# Irrigate4.net
KiCad netlist of a schematic drawn in EAGLE
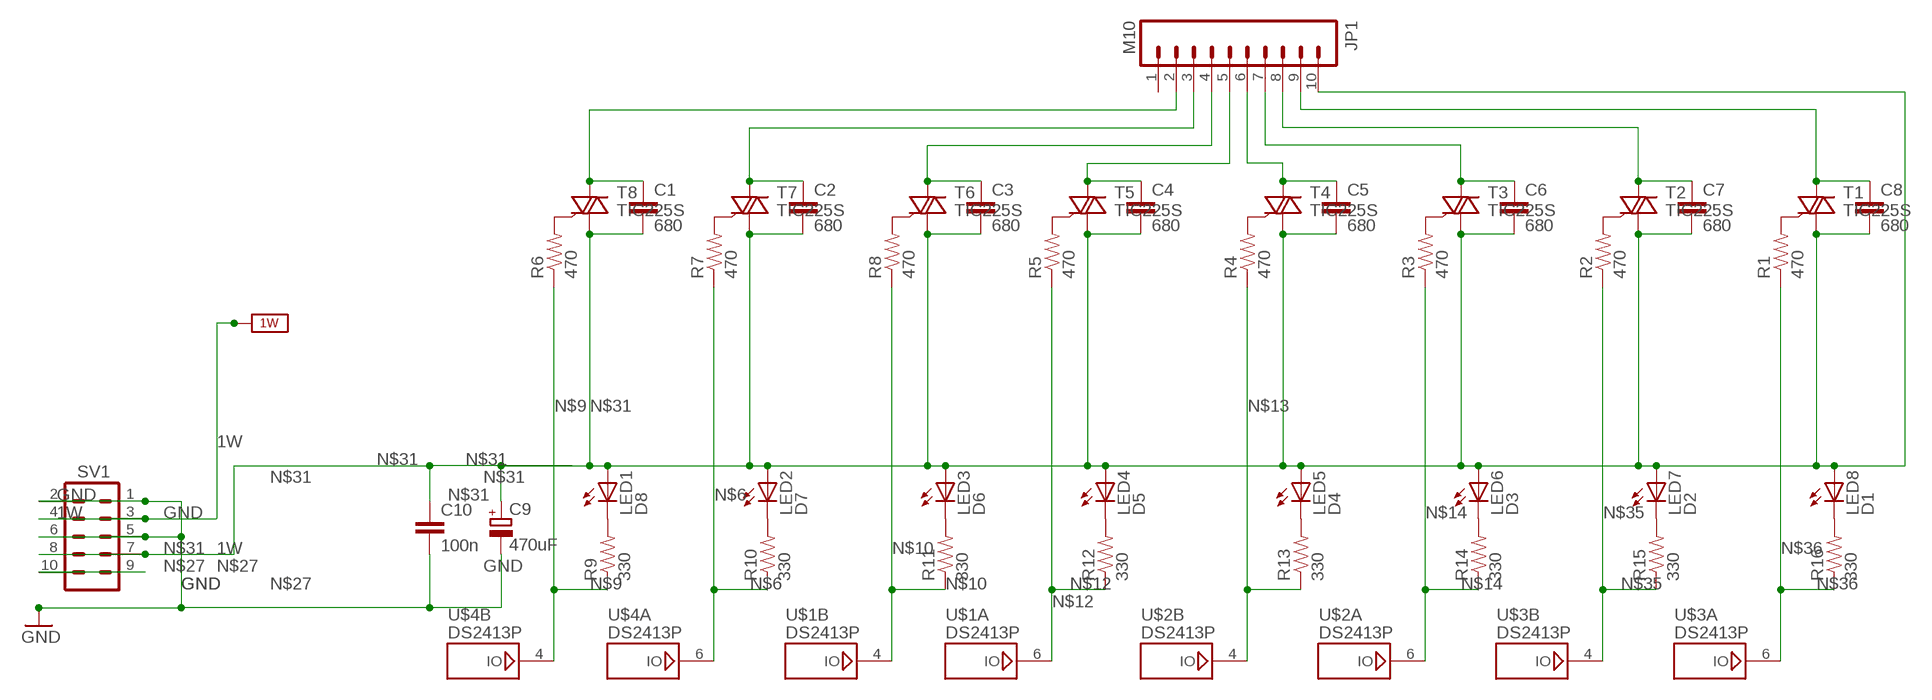
[diagram p0: schematic, sheet 1]

(export (version "E")
  (design (tool "Eeschema 10.0.6"))
  (components
    (comp (ref "C1")
      (value "680")
      (footprint "eagle-import:C050-045X075")
      (libsource (lib "eagle-import") (part "C-EU050-045X075"))
    )
    (comp (ref "C2")
      (value "680")
      (footprint "eagle-import:C050-045X075")
      (libsource (lib "eagle-import") (part "C-EU050-045X075"))
    )
    (comp (ref "C3")
      (value "680")
      (footprint "eagle-import:C050-045X075")
      (libsource (lib "eagle-import") (part "C-EU050-045X075"))
    )
    (comp (ref "C4")
      (value "680")
      (footprint "eagle-import:C050-045X075")
      (libsource (lib "eagle-import") (part "C-EU050-045X075"))
    )
    (comp (ref "C5")
      (value "680")
      (footprint "eagle-import:C050-045X075")
      (libsource (lib "eagle-import") (part "C-EU050-045X075"))
    )
    (comp (ref "C6")
      (value "680")
      (footprint "eagle-import:C050-045X075")
      (libsource (lib "eagle-import") (part "C-EU050-045X075"))
    )
    (comp (ref "C7")
      (value "680")
      (footprint "eagle-import:C050-045X075")
      (libsource (lib "eagle-import") (part "C-EU050-045X075"))
    )
    (comp (ref "C8")
      (value "680")
      (footprint "eagle-import:C050-045X075")
      (libsource (lib "eagle-import") (part "C-EU050-045X075"))
    )
    (comp (ref "C9")
      (value "470uF")
      (footprint "eagle-import:E5-8,5")
      (libsource (lib "eagle-import") (part "CPOL-EUE5-8.5"))
    )
    (comp (ref "C10")
      (value "100n")
      (footprint "eagle-import:C050-024X044")
      (libsource (lib "eagle-import") (part "C-EU050-024X044"))
    )
    (comp (ref "JP1")
      (value "M10")
      (footprint "eagle-import:10X10MM")
      (libsource (lib "eagle-import") (part "M10"))
    )
    (comp (ref "LED1")
      (value "D8")
      (footprint "eagle-import:LED3MM")
      (libsource (lib "eagle-import") (part "LED3MM"))
    )
    (comp (ref "LED2")
      (value "D7")
      (footprint "eagle-import:LED3MM")
      (libsource (lib "eagle-import") (part "LED3MM"))
    )
    (comp (ref "LED3")
      (value "D6")
      (footprint "eagle-import:LED3MM")
      (libsource (lib "eagle-import") (part "LED3MM"))
    )
    (comp (ref "LED4")
      (value "D5")
      (footprint "eagle-import:LED3MM")
      (libsource (lib "eagle-import") (part "LED3MM"))
    )
    (comp (ref "LED5")
      (value "D4")
      (footprint "eagle-import:LED3MM")
      (libsource (lib "eagle-import") (part "LED3MM"))
    )
    (comp (ref "LED6")
      (value "D3")
      (footprint "eagle-import:LED3MM")
      (libsource (lib "eagle-import") (part "LED3MM"))
    )
    (comp (ref "LED7")
      (value "D2")
      (footprint "eagle-import:LED3MM")
      (libsource (lib "eagle-import") (part "LED3MM"))
    )
    (comp (ref "LED8")
      (value "D1")
      (footprint "eagle-import:LED3MM")
      (libsource (lib "eagle-import") (part "LED3MM"))
    )
    (comp (ref "R1")
      (value "470")
      (footprint "eagle-import:AXIAL-0.3")
      (libsource (lib "eagle-import") (part "RESISTORPTH1"))
    )
    (comp (ref "R2")
      (value "470")
      (footprint "eagle-import:AXIAL-0.3")
      (libsource (lib "eagle-import") (part "RESISTORPTH1"))
    )
    (comp (ref "R3")
      (value "470")
      (footprint "eagle-import:AXIAL-0.3")
      (libsource (lib "eagle-import") (part "RESISTORPTH1"))
    )
    (comp (ref "R4")
      (value "470")
      (footprint "eagle-import:AXIAL-0.3")
      (libsource (lib "eagle-import") (part "RESISTORPTH1"))
    )
    (comp (ref "R5")
      (value "470")
      (footprint "eagle-import:AXIAL-0.3")
      (libsource (lib "eagle-import") (part "RESISTORPTH1"))
    )
    (comp (ref "R6")
      (value "470")
      (footprint "eagle-import:AXIAL-0.3")
      (libsource (lib "eagle-import") (part "RESISTORPTH1"))
    )
    (comp (ref "R7")
      (value "470")
      (footprint "eagle-import:AXIAL-0.3")
      (libsource (lib "eagle-import") (part "RESISTORPTH1"))
    )
    (comp (ref "R8")
      (value "470")
      (footprint "eagle-import:AXIAL-0.3")
      (libsource (lib "eagle-import") (part "RESISTORPTH1"))
    )
    (comp (ref "R9")
      (value "330")
      (footprint "eagle-import:AXIAL-0.3")
      (libsource (lib "eagle-import") (part "RESISTORPTH1"))
    )
    (comp (ref "R10")
      (value "330")
      (footprint "eagle-import:AXIAL-0.3")
      (libsource (lib "eagle-import") (part "RESISTORPTH1"))
    )
    (comp (ref "R11")
      (value "330")
      (footprint "eagle-import:AXIAL-0.3")
      (libsource (lib "eagle-import") (part "RESISTORPTH1"))
    )
    (comp (ref "R12")
      (value "330")
      (footprint "eagle-import:AXIAL-0.3")
      (libsource (lib "eagle-import") (part "RESISTORPTH1"))
    )
    (comp (ref "R13")
      (value "330")
      (footprint "eagle-import:AXIAL-0.3")
      (libsource (lib "eagle-import") (part "RESISTORPTH1"))
    )
    (comp (ref "R14")
      (value "330")
      (footprint "eagle-import:AXIAL-0.3")
      (libsource (lib "eagle-import") (part "RESISTORPTH1"))
    )
    (comp (ref "R15")
      (value "330")
      (footprint "eagle-import:AXIAL-0.3")
      (libsource (lib "eagle-import") (part "RESISTORPTH1"))
    )
    (comp (ref "R16")
      (value "330")
      (footprint "eagle-import:AXIAL-0.3")
      (libsource (lib "eagle-import") (part "RESISTORPTH1"))
    )
    (comp (ref "SV1")
      (value "M05X2PTH")
      (footprint "eagle-import:AVR_ICSP")
      (libsource (lib "eagle-import") (part "M05X2PTH"))
    )
    (comp (ref "T1")
      (value "TIC225S")
      (footprint "eagle-import:TO220DS")
      (libsource (lib "eagle-import") (part "TIC225S"))
    )
    (comp (ref "T2")
      (value "TIC225S")
      (footprint "eagle-import:TO220DS")
      (libsource (lib "eagle-import") (part "TIC225S"))
    )
    (comp (ref "T3")
      (value "TIC225S")
      (footprint "eagle-import:TO220DS")
      (libsource (lib "eagle-import") (part "TIC225S"))
    )
    (comp (ref "T4")
      (value "TIC225S")
      (footprint "eagle-import:TO220DS")
      (libsource (lib "eagle-import") (part "TIC225S"))
    )
    (comp (ref "T5")
      (value "TIC225S")
      (footprint "eagle-import:TO220DS")
      (libsource (lib "eagle-import") (part "TIC225S"))
    )
    (comp (ref "T6")
      (value "TIC225S")
      (footprint "eagle-import:TO220DS")
      (libsource (lib "eagle-import") (part "TIC225S"))
    )
    (comp (ref "T7")
      (value "TIC225S")
      (footprint "eagle-import:TO220DS")
      (libsource (lib "eagle-import") (part "TIC225S"))
    )
    (comp (ref "T8")
      (value "TIC225S")
      (footprint "eagle-import:TO220DS")
      (libsource (lib "eagle-import") (part "TIC225S"))
    )
    (comp (ref "U$1")
      (value "DS2413P")
      (footprint "eagle-import:TSOC6")
      (libsource (lib "eagle-import") (part "DS2413P"))
    )
    (comp (ref "U$2")
      (value "DS2413P")
      (footprint "eagle-import:TSOC6")
      (libsource (lib "eagle-import") (part "DS2413P"))
    )
    (comp (ref "U$3")
      (value "DS2413P")
      (footprint "eagle-import:TSOC6")
      (libsource (lib "eagle-import") (part "DS2413P"))
    )
    (comp (ref "U$4")
      (value "DS2413P")
      (footprint "eagle-import:TSOC6")
      (libsource (lib "eagle-import") (part "DS2413P"))
    )
  )
  (nets
    (net (code "1") (name "/N$6") (class "Default")
      (node (ref "R10") (pin "P$1") (pinfunction "1_P$1") (pintype "passive"))
      (node (ref "R7") (pin "P$1") (pinfunction "1_P$1") (pintype "passive"))
      (node (ref "U$4") (pin "6") (pinfunction "IO_6") (pintype "open_collector"))
    )
    (net (code "2") (name "/N$9") (class "Default")
      (node (ref "R6") (pin "P$1") (pinfunction "1_P$1") (pintype "passive"))
      (node (ref "R9") (pin "P$1") (pinfunction "1_P$1") (pintype "passive"))
      (node (ref "U$4") (pin "4") (pinfunction "IO_4") (pintype "open_collector"))
    )
    (net (code "3") (name "/N$10") (class "Default")
      (node (ref "R11") (pin "P$1") (pinfunction "1_P$1") (pintype "passive"))
      (node (ref "R8") (pin "P$1") (pinfunction "1_P$1") (pintype "passive"))
      (node (ref "U$1") (pin "4") (pinfunction "IO_4") (pintype "open_collector"))
    )
    (net (code "4") (name "/N$12") (class "Default")
      (node (ref "R12") (pin "P$1") (pinfunction "1_P$1") (pintype "passive"))
      (node (ref "R5") (pin "P$1") (pinfunction "1_P$1") (pintype "passive"))
      (node (ref "U$1") (pin "6") (pinfunction "IO_6") (pintype "open_collector"))
    )
    (net (code "5") (name "/N$13") (class "Default")
      (node (ref "R13") (pin "P$1") (pinfunction "1_P$1") (pintype "passive"))
      (node (ref "R4") (pin "P$1") (pinfunction "1_P$1") (pintype "passive"))
      (node (ref "U$2") (pin "4") (pinfunction "IO_4") (pintype "open_collector"))
    )
    (net (code "6") (name "/N$14") (class "Default")
      (node (ref "R14") (pin "P$1") (pinfunction "1_P$1") (pintype "passive"))
      (node (ref "R3") (pin "P$1") (pinfunction "1_P$1") (pintype "passive"))
      (node (ref "U$2") (pin "6") (pinfunction "IO_6") (pintype "open_collector"))
    )
    (net (code "7") (name "/N$27") (class "Default")
      (node (ref "SV1") (pin "10") (pinfunction "10_10") (pintype "passive"))
      (node (ref "SV1") (pin "9") (pinfunction "9_9") (pintype "passive"))
    )
    (net (code "8") (name "/N$31") (class "Default")
      (node (ref "C1") (pin "2") (pinfunction "2_2") (pintype "passive"))
      (node (ref "C10") (pin "1") (pinfunction "1_1") (pintype "passive"))
      (node (ref "C2") (pin "2") (pinfunction "2_2") (pintype "passive"))
      (node (ref "C3") (pin "2") (pinfunction "2_2") (pintype "passive"))
      (node (ref "C4") (pin "2") (pinfunction "2_2") (pintype "passive"))
      (node (ref "C5") (pin "2") (pinfunction "2_2") (pintype "passive"))
      (node (ref "C6") (pin "2") (pinfunction "2_2") (pintype "passive"))
      (node (ref "C7") (pin "2") (pinfunction "2_2") (pintype "passive"))
      (node (ref "C8") (pin "2") (pinfunction "2_2") (pintype "passive"))
      (node (ref "C9") (pin "+") (pinfunction "+_+") (pintype "passive"))
      (node (ref "JP1") (pin "10") (pinfunction "10_10") (pintype "passive"))
      (node (ref "LED1") (pin "A") (pinfunction "A_A") (pintype "passive"))
      (node (ref "LED2") (pin "A") (pinfunction "A_A") (pintype "passive"))
      (node (ref "LED3") (pin "A") (pinfunction "A_A") (pintype "passive"))
      (node (ref "LED4") (pin "A") (pinfunction "A_A") (pintype "passive"))
      (node (ref "LED5") (pin "A") (pinfunction "A_A") (pintype "passive"))
      (node (ref "LED6") (pin "A") (pinfunction "A_A") (pintype "passive"))
      (node (ref "LED7") (pin "A") (pinfunction "A_A") (pintype "passive"))
      (node (ref "LED8") (pin "A") (pinfunction "A_A") (pintype "passive"))
      (node (ref "SV1") (pin "7") (pinfunction "7_7") (pintype "passive"))
      (node (ref "SV1") (pin "8") (pinfunction "8_8") (pintype "passive"))
      (node (ref "T1") (pin "A1") (pinfunction "A1_A1") (pintype "passive"))
      (node (ref "T2") (pin "A1") (pinfunction "A1_A1") (pintype "passive"))
      (node (ref "T3") (pin "A1") (pinfunction "A1_A1") (pintype "passive"))
      (node (ref "T4") (pin "A1") (pinfunction "A1_A1") (pintype "passive"))
      (node (ref "T5") (pin "A1") (pinfunction "A1_A1") (pintype "passive"))
      (node (ref "T6") (pin "A1") (pinfunction "A1_A1") (pintype "passive"))
      (node (ref "T7") (pin "A1") (pinfunction "A1_A1") (pintype "passive"))
      (node (ref "T8") (pin "A1") (pinfunction "A1_A1") (pintype "passive"))
    )
    (net (code "9") (name "/N$35") (class "Default")
      (node (ref "R15") (pin "P$1") (pinfunction "1_P$1") (pintype "passive"))
      (node (ref "R2") (pin "P$1") (pinfunction "1_P$1") (pintype "passive"))
      (node (ref "U$3") (pin "4") (pinfunction "IO_4") (pintype "open_collector"))
    )
    (net (code "10") (name "/N$36") (class "Default")
      (node (ref "R1") (pin "P$1") (pinfunction "1_P$1") (pintype "passive"))
      (node (ref "R16") (pin "P$1") (pinfunction "1_P$1") (pintype "passive"))
      (node (ref "U$3") (pin "6") (pinfunction "IO_6") (pintype "open_collector"))
    )
    (net (code "11") (name "1W_SUP") (class "Default")
      (node (ref "SV1") (pin "3") (pinfunction "3_3") (pintype "passive"))
      (node (ref "SV1") (pin "4") (pinfunction "4_4") (pintype "passive"))
    )
    (net (code "12") (name "GND") (class "Default")
      (node (ref "C10") (pin "2") (pinfunction "2_2") (pintype "passive"))
      (node (ref "C9") (pin "-") (pinfunction "-_-") (pintype "passive"))
      (node (ref "SV1") (pin "1") (pinfunction "1_1") (pintype "passive"))
      (node (ref "SV1") (pin "2") (pinfunction "2_2") (pintype "passive"))
      (node (ref "SV1") (pin "5") (pinfunction "5_5") (pintype "passive"))
      (node (ref "SV1") (pin "6") (pinfunction "6_6") (pintype "passive"))
    )
    (net (code "13") (name "Net-(C1-Pad1)") (class "Default")
      (node (ref "C1") (pin "1") (pinfunction "1_1") (pintype "passive"))
      (node (ref "JP1") (pin "2") (pinfunction "2_2") (pintype "passive"))
      (node (ref "T8") (pin "A2") (pinfunction "A2_A2") (pintype "passive"))
    )
    (net (code "14") (name "Net-(C2-Pad1)") (class "Default")
      (node (ref "C2") (pin "1") (pinfunction "1_1") (pintype "passive"))
      (node (ref "JP1") (pin "3") (pinfunction "3_3") (pintype "passive"))
      (node (ref "T7") (pin "A2") (pinfunction "A2_A2") (pintype "passive"))
    )
    (net (code "15") (name "Net-(C3-Pad1)") (class "Default")
      (node (ref "C3") (pin "1") (pinfunction "1_1") (pintype "passive"))
      (node (ref "JP1") (pin "4") (pinfunction "4_4") (pintype "passive"))
      (node (ref "T6") (pin "A2") (pinfunction "A2_A2") (pintype "passive"))
    )
    (net (code "16") (name "Net-(C4-Pad1)") (class "Default")
      (node (ref "C4") (pin "1") (pinfunction "1_1") (pintype "passive"))
      (node (ref "JP1") (pin "5") (pinfunction "5_5") (pintype "passive"))
      (node (ref "T5") (pin "A2") (pinfunction "A2_A2") (pintype "passive"))
    )
    (net (code "17") (name "Net-(C5-Pad1)") (class "Default")
      (node (ref "C5") (pin "1") (pinfunction "1_1") (pintype "passive"))
      (node (ref "JP1") (pin "6") (pinfunction "6_6") (pintype "passive"))
      (node (ref "T4") (pin "A2") (pinfunction "A2_A2") (pintype "passive"))
    )
    (net (code "18") (name "Net-(C6-Pad1)") (class "Default")
      (node (ref "C6") (pin "1") (pinfunction "1_1") (pintype "passive"))
      (node (ref "JP1") (pin "7") (pinfunction "7_7") (pintype "passive"))
      (node (ref "T3") (pin "A2") (pinfunction "A2_A2") (pintype "passive"))
    )
    (net (code "19") (name "Net-(C7-Pad1)") (class "Default")
      (node (ref "C7") (pin "1") (pinfunction "1_1") (pintype "passive"))
      (node (ref "JP1") (pin "8") (pinfunction "8_8") (pintype "passive"))
      (node (ref "T2") (pin "A2") (pinfunction "A2_A2") (pintype "passive"))
    )
    (net (code "20") (name "Net-(C8-Pad1)") (class "Default")
      (node (ref "C8") (pin "1") (pinfunction "1_1") (pintype "passive"))
      (node (ref "JP1") (pin "9") (pinfunction "9_9") (pintype "passive"))
      (node (ref "T1") (pin "A2") (pinfunction "A2_A2") (pintype "passive"))
    )
    (net (code "21") (name "Net-(LED1-C)") (class "Default")
      (node (ref "LED1") (pin "K") (pinfunction "C_K") (pintype "passive"))
      (node (ref "R9") (pin "P$2") (pinfunction "2_P$2") (pintype "passive"))
    )
    (net (code "22") (name "Net-(LED2-C)") (class "Default")
      (node (ref "LED2") (pin "K") (pinfunction "C_K") (pintype "passive"))
      (node (ref "R10") (pin "P$2") (pinfunction "2_P$2") (pintype "passive"))
    )
    (net (code "23") (name "Net-(LED3-C)") (class "Default")
      (node (ref "LED3") (pin "K") (pinfunction "C_K") (pintype "passive"))
      (node (ref "R11") (pin "P$2") (pinfunction "2_P$2") (pintype "passive"))
    )
    (net (code "24") (name "Net-(LED4-C)") (class "Default")
      (node (ref "LED4") (pin "K") (pinfunction "C_K") (pintype "passive"))
      (node (ref "R12") (pin "P$2") (pinfunction "2_P$2") (pintype "passive"))
    )
    (net (code "25") (name "Net-(LED5-C)") (class "Default")
      (node (ref "LED5") (pin "K") (pinfunction "C_K") (pintype "passive"))
      (node (ref "R13") (pin "P$2") (pinfunction "2_P$2") (pintype "passive"))
    )
    (net (code "26") (name "Net-(LED6-C)") (class "Default")
      (node (ref "LED6") (pin "K") (pinfunction "C_K") (pintype "passive"))
      (node (ref "R14") (pin "P$2") (pinfunction "2_P$2") (pintype "passive"))
    )
    (net (code "27") (name "Net-(LED7-C)") (class "Default")
      (node (ref "LED7") (pin "K") (pinfunction "C_K") (pintype "passive"))
      (node (ref "R15") (pin "P$2") (pinfunction "2_P$2") (pintype "passive"))
    )
    (net (code "28") (name "Net-(LED8-C)") (class "Default")
      (node (ref "LED8") (pin "K") (pinfunction "C_K") (pintype "passive"))
      (node (ref "R16") (pin "P$2") (pinfunction "2_P$2") (pintype "passive"))
    )
    (net (code "29") (name "Net-(R1-2)") (class "Default")
      (node (ref "R1") (pin "P$2") (pinfunction "2_P$2") (pintype "passive"))
      (node (ref "T1") (pin "G") (pinfunction "G_G") (pintype "passive"))
    )
    (net (code "30") (name "Net-(R2-2)") (class "Default")
      (node (ref "R2") (pin "P$2") (pinfunction "2_P$2") (pintype "passive"))
      (node (ref "T2") (pin "G") (pinfunction "G_G") (pintype "passive"))
    )
    (net (code "31") (name "Net-(R3-2)") (class "Default")
      (node (ref "R3") (pin "P$2") (pinfunction "2_P$2") (pintype "passive"))
      (node (ref "T3") (pin "G") (pinfunction "G_G") (pintype "passive"))
    )
    (net (code "32") (name "Net-(R4-2)") (class "Default")
      (node (ref "R4") (pin "P$2") (pinfunction "2_P$2") (pintype "passive"))
      (node (ref "T4") (pin "G") (pinfunction "G_G") (pintype "passive"))
    )
    (net (code "33") (name "Net-(R5-2)") (class "Default")
      (node (ref "R5") (pin "P$2") (pinfunction "2_P$2") (pintype "passive"))
      (node (ref "T5") (pin "G") (pinfunction "G_G") (pintype "passive"))
    )
    (net (code "34") (name "Net-(R6-2)") (class "Default")
      (node (ref "R6") (pin "P$2") (pinfunction "2_P$2") (pintype "passive"))
      (node (ref "T8") (pin "G") (pinfunction "G_G") (pintype "passive"))
    )
    (net (code "35") (name "Net-(R7-2)") (class "Default")
      (node (ref "R7") (pin "P$2") (pinfunction "2_P$2") (pintype "passive"))
      (node (ref "T7") (pin "G") (pinfunction "G_G") (pintype "passive"))
    )
    (net (code "36") (name "Net-(R8-2)") (class "Default")
      (node (ref "R8") (pin "P$2") (pinfunction "2_P$2") (pintype "passive"))
      (node (ref "T6") (pin "G") (pinfunction "G_G") (pintype "passive"))
    )
    (net (code "37") (name "unconnected-(JP1-Pad1)") (class "Default")
      (node (ref "JP1") (pin "1") (pinfunction "1_1") (pintype "passive"))
    )
  )
)
